# LCD_TFT.net
KiCad netlist of a schematic drawn in Altium Designer
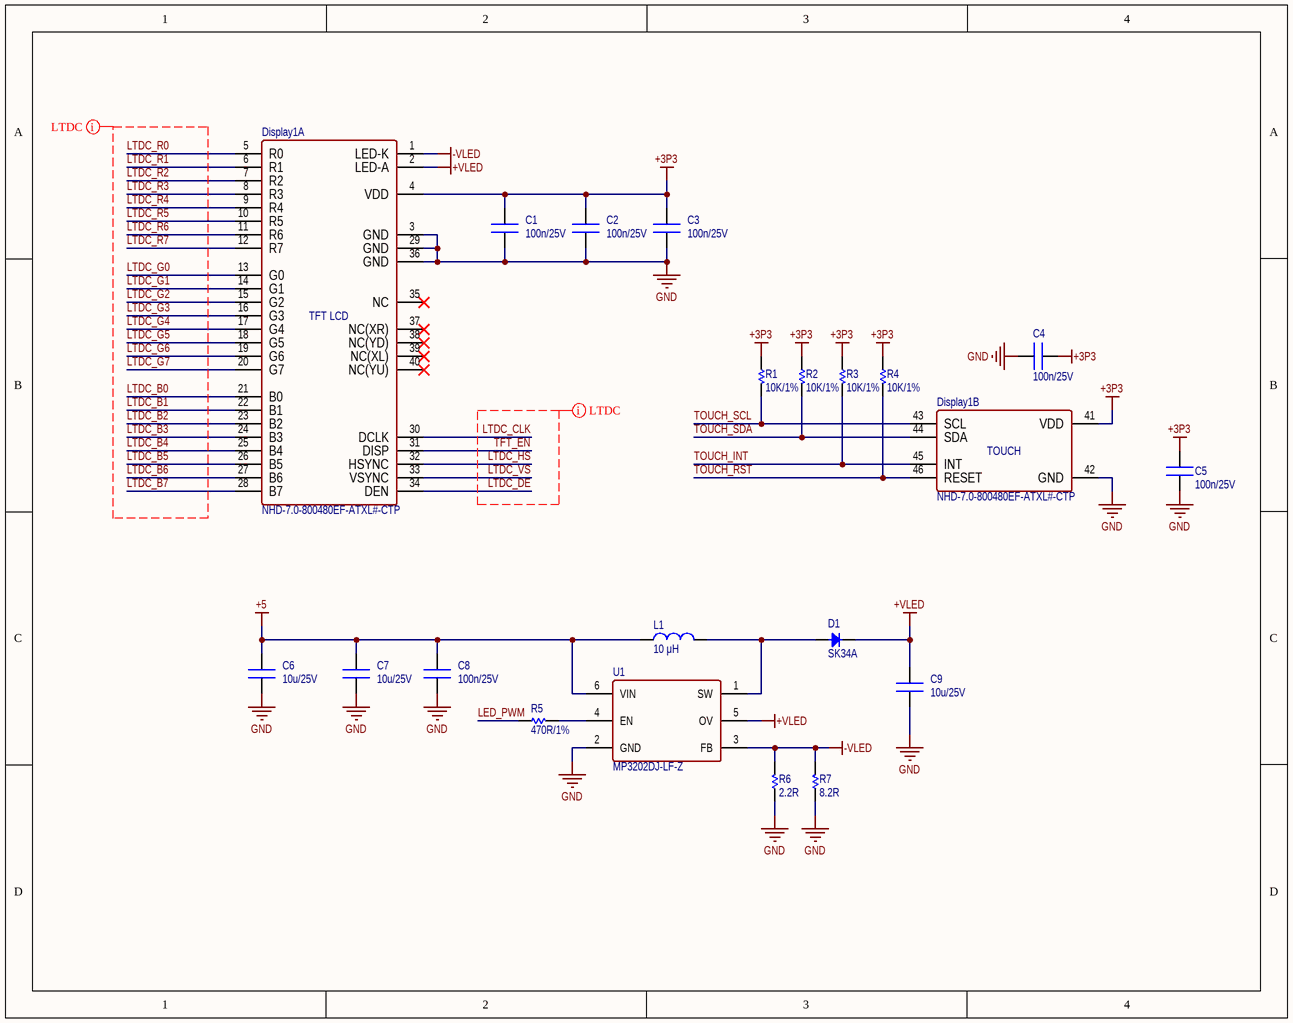
[diagram p0: LCD_TFT.SchDoc]

(export (version "E")
  (design (tool "Eeschema 10.0.6"))
  (components
    (comp (ref "C1")
      (value "100n/25V")
      (footprint "CN-SMD-0603")
      (description "CL10B104KA8NNNC")
      (libsource (lib "Library") (part "CN"))
    )
    (comp (ref "C2")
      (value "100n/25V")
      (footprint "CN-SMD-0603")
      (description "CL10B104KA8NNNC")
      (libsource (lib "Library") (part "CN"))
    )
    (comp (ref "C3")
      (value "100n/25V")
      (footprint "CN-SMD-0603")
      (description "CL10B104KA8NNNC")
      (libsource (lib "Library") (part "CN"))
    )
    (comp (ref "C4")
      (value "100n/25V")
      (footprint "CN-SMD-0603")
      (description "CL10B104KA8NNNC")
      (libsource (lib "Library") (part "CN"))
    )
    (comp (ref "C5")
      (value "100n/25V")
      (footprint "CN-SMD-0603")
      (description "CL10B104KA8NNNC")
      (libsource (lib "Library") (part "CN"))
    )
    (comp (ref "C6")
      (value "10u/25V")
      (footprint "CN-SMD-0603")
      (description "0603W106M250XD")
      (libsource (lib "Library") (part "CN"))
    )
    (comp (ref "C7")
      (value "10u/25V")
      (footprint "CN-SMD-0603")
      (description "0603W106M250XD")
      (libsource (lib "Library") (part "CN"))
    )
    (comp (ref "C8")
      (value "100n/25V")
      (footprint "CN-SMD-0603")
      (description "CL10B104KA8NNNC")
      (libsource (lib "Library") (part "CN"))
    )
    (comp (ref "C9")
      (value "10u/25V")
      (footprint "CN-SMD-0603")
      (description "0603W106M250XD")
      (libsource (lib "Library") (part "CN"))
    )
    (comp (ref "D1")
      (value "SK34A")
      (footprint "DIO-SMD-A")
      (fields (field (name "PUBLISHER") "Altium Limited"))
      (libsource (lib "Library") (part "Diode SMD"))
    )
    (comp (ref "Display1")
      (value "NHD-7.0-800480EF-ATXL#-CTP")
      (footprint "NHD-7.0-800480EF-ATXL#-CTP")
      (description "TFT (Thin-Film-Transistor) Color Liquid Crystal Display Module, 0541044031 + 52271-0679")
      (libsource (lib "Library") (part "NHD-7.0-800480EF-ATXL#-CTP"))
    )
    (comp (ref "L1")
      (value "10 μH")
      (footprint "L-SMD-M-5x5")
      (description "NRS5024T100MMGJ")
      (fields (field (name "MANUFACTURER") "Wurth Elektronik") (field (name "CREATED BY") "Baojun Chen"))
      (libsource (lib "Library") (part "L-SMD-1"))
    )
    (comp (ref "R1")
      (value "10K/1%")
      (footprint "RES-SMD-0603")
      (description "ERJ-3EKF1002V")
      (fields
        (field (name "MANUFACTURER") "Generic Components")
        (field (name "PUBLISHER") "Altium Hobart Technology Centre")
      )
      (libsource (lib "Library") (part "Res-SMD"))
    )
    (comp (ref "R2")
      (value "10K/1%")
      (footprint "RES-SMD-0603")
      (description "ERJ-3EKF1002V")
      (fields
        (field (name "MANUFACTURER") "Generic Components")
        (field (name "PUBLISHER") "Altium Hobart Technology Centre")
      )
      (libsource (lib "Library") (part "Res-SMD"))
    )
    (comp (ref "R3")
      (value "10K/1%")
      (footprint "RES-SMD-0603")
      (description "ERJ-3EKF1002V")
      (fields
        (field (name "MANUFACTURER") "Generic Components")
        (field (name "PUBLISHER") "Altium Hobart Technology Centre")
      )
      (libsource (lib "Library") (part "Res-SMD"))
    )
    (comp (ref "R4")
      (value "10K/1%")
      (footprint "RES-SMD-0603")
      (description "ERJ-3EKF1002V")
      (fields
        (field (name "MANUFACTURER") "Generic Components")
        (field (name "PUBLISHER") "Altium Hobart Technology Centre")
      )
      (libsource (lib "Library") (part "Res-SMD"))
    )
    (comp (ref "R5")
      (value "470R/1%")
      (footprint "RES-SMD-0603")
      (description "ERJ-1GJF4700C")
      (fields
        (field (name "MANUFACTURER") "Generic Components")
        (field (name "PUBLISHER") "Altium Hobart Technology Centre")
      )
      (libsource (lib "Library") (part "Res-SMD"))
    )
    (comp (ref "R6")
      (value "2.2R")
      (footprint "RES-SMD-0805")
      (description "RMCF0805JT2R20")
      (fields
        (field (name "MANUFACTURER") "Generic Components")
        (field (name "PUBLISHER") "Altium Hobart Technology Centre")
      )
      (libsource (lib "Library") (part "Res-SMD"))
    )
    (comp (ref "R7")
      (value "8.2R")
      (footprint "RES-SMD-0805")
      (description "RMCF0805FT8R20")
      (fields
        (field (name "MANUFACTURER") "Generic Components")
        (field (name "PUBLISHER") "Altium Hobart Technology Centre")
      )
      (libsource (lib "Library") (part "Res-SMD"))
    )
    (comp (ref "U1")
      (value "MP3202DJ-LF-Z")
      (footprint "SOT23-6")
      (description "1.3A Fixed Frequency White LED Driver")
      (libsource (lib "Library") (part "MP3202"))
    )
  )
  (nets
    (net (code "1") (name "+3P3") (class "Default")
      (node (ref "C1") (pin "2") (pinfunction "2_2") (pintype "passive"))
      (node (ref "C2") (pin "2") (pinfunction "2_2") (pintype "passive"))
      (node (ref "C3") (pin "2") (pinfunction "2_2") (pintype "passive"))
      (node (ref "C4") (pin "2") (pinfunction "2_2") (pintype "passive"))
      (node (ref "C5") (pin "2") (pinfunction "2_2") (pintype "passive"))
      (node (ref "Display1") (pin "4") (pinfunction "VDD_4") (pintype "passive"))
      (node (ref "Display1") (pin "41") (pinfunction "VDD_41") (pintype "passive"))
      (node (ref "R1") (pin "1") (pinfunction "1_1") (pintype "passive"))
      (node (ref "R2") (pin "1") (pinfunction "1_1") (pintype "passive"))
      (node (ref "R3") (pin "1") (pinfunction "1_1") (pintype "passive"))
      (node (ref "R4") (pin "1") (pinfunction "1_1") (pintype "passive"))
    )
    (net (code "2") (name "+5") (class "Default")
      (node (ref "C6") (pin "2") (pinfunction "2_2") (pintype "passive"))
      (node (ref "C7") (pin "2") (pinfunction "2_2") (pintype "passive"))
      (node (ref "C8") (pin "2") (pinfunction "2_2") (pintype "passive"))
      (node (ref "L1") (pin "1") (pinfunction "1_1") (pintype "passive"))
      (node (ref "U1") (pin "6") (pinfunction "VIN_6") (pintype "passive"))
    )
    (net (code "3") (name "+VLED") (class "Default")
      (node (ref "C9") (pin "2") (pinfunction "2_2") (pintype "passive"))
      (node (ref "D1") (pin "2") (pinfunction "K_2") (pintype "passive"))
      (node (ref "Display1") (pin "2") (pinfunction "LED-A_2") (pintype "passive"))
      (node (ref "U1") (pin "5") (pinfunction "OV_5") (pintype "passive"))
    )
    (net (code "4") (name "-VLED") (class "Default")
      (node (ref "Display1") (pin "1") (pinfunction "LED-K_1") (pintype "passive"))
      (node (ref "R6") (pin "2") (pinfunction "2_2") (pintype "passive"))
      (node (ref "R7") (pin "2") (pinfunction "2_2") (pintype "passive"))
      (node (ref "U1") (pin "3") (pinfunction "FB_3") (pintype "passive"))
    )
    (net (code "5") (name "/LED_PWM") (class "Default")
      (node (ref "R5") (pin "1") (pinfunction "1_1") (pintype "passive"))
    )
    (net (code "6") (name "/LTDC_B0") (class "Default")
      (node (ref "Display1") (pin "21") (pinfunction "B0_21") (pintype "passive"))
    )
    (net (code "7") (name "/LTDC_B1") (class "Default")
      (node (ref "Display1") (pin "22") (pinfunction "B1_22") (pintype "passive"))
    )
    (net (code "8") (name "/LTDC_B2") (class "Default")
      (node (ref "Display1") (pin "23") (pinfunction "B2_23") (pintype "passive"))
    )
    (net (code "9") (name "/LTDC_B3") (class "Default")
      (node (ref "Display1") (pin "24") (pinfunction "B3_24") (pintype "passive"))
    )
    (net (code "10") (name "/LTDC_B4") (class "Default")
      (node (ref "Display1") (pin "25") (pinfunction "B4_25") (pintype "passive"))
    )
    (net (code "11") (name "/LTDC_B5") (class "Default")
      (node (ref "Display1") (pin "26") (pinfunction "B5_26") (pintype "passive"))
    )
    (net (code "12") (name "/LTDC_B6") (class "Default")
      (node (ref "Display1") (pin "27") (pinfunction "B6_27") (pintype "passive"))
    )
    (net (code "13") (name "/LTDC_B7") (class "Default")
      (node (ref "Display1") (pin "28") (pinfunction "B7_28") (pintype "passive"))
    )
    (net (code "14") (name "/LTDC_CLK") (class "Default")
      (node (ref "Display1") (pin "30") (pinfunction "DCLK_30") (pintype "passive"))
    )
    (net (code "15") (name "/LTDC_DE") (class "Default")
      (node (ref "Display1") (pin "34") (pinfunction "DEN_34") (pintype "passive"))
    )
    (net (code "16") (name "/LTDC_G0") (class "Default")
      (node (ref "Display1") (pin "13") (pinfunction "G0_13") (pintype "passive"))
    )
    (net (code "17") (name "/LTDC_G1") (class "Default")
      (node (ref "Display1") (pin "14") (pinfunction "G1_14") (pintype "passive"))
    )
    (net (code "18") (name "/LTDC_G2") (class "Default")
      (node (ref "Display1") (pin "15") (pinfunction "G2_15") (pintype "passive"))
    )
    (net (code "19") (name "/LTDC_G3") (class "Default")
      (node (ref "Display1") (pin "16") (pinfunction "G3_16") (pintype "passive"))
    )
    (net (code "20") (name "/LTDC_G4") (class "Default")
      (node (ref "Display1") (pin "17") (pinfunction "G4_17") (pintype "passive"))
    )
    (net (code "21") (name "/LTDC_G5") (class "Default")
      (node (ref "Display1") (pin "18") (pinfunction "G5_18") (pintype "passive"))
    )
    (net (code "22") (name "/LTDC_G6") (class "Default")
      (node (ref "Display1") (pin "19") (pinfunction "G6_19") (pintype "passive"))
    )
    (net (code "23") (name "/LTDC_G7") (class "Default")
      (node (ref "Display1") (pin "20") (pinfunction "G7_20") (pintype "passive"))
    )
    (net (code "24") (name "/LTDC_HS") (class "Default")
      (node (ref "Display1") (pin "32") (pinfunction "HSYNC_32") (pintype "passive"))
    )
    (net (code "25") (name "/LTDC_R0") (class "Default")
      (node (ref "Display1") (pin "5") (pinfunction "R0_5") (pintype "passive"))
    )
    (net (code "26") (name "/LTDC_R1") (class "Default")
      (node (ref "Display1") (pin "6") (pinfunction "R1_6") (pintype "passive"))
    )
    (net (code "27") (name "/LTDC_R2") (class "Default")
      (node (ref "Display1") (pin "7") (pinfunction "R2_7") (pintype "passive"))
    )
    (net (code "28") (name "/LTDC_R3") (class "Default")
      (node (ref "Display1") (pin "8") (pinfunction "R3_8") (pintype "passive"))
    )
    (net (code "29") (name "/LTDC_R4") (class "Default")
      (node (ref "Display1") (pin "9") (pinfunction "R4_9") (pintype "passive"))
    )
    (net (code "30") (name "/LTDC_R5") (class "Default")
      (node (ref "Display1") (pin "10") (pinfunction "R5_10") (pintype "passive"))
    )
    (net (code "31") (name "/LTDC_R6") (class "Default")
      (node (ref "Display1") (pin "11") (pinfunction "R6_11") (pintype "passive"))
    )
    (net (code "32") (name "/LTDC_R7") (class "Default")
      (node (ref "Display1") (pin "12") (pinfunction "R7_12") (pintype "passive"))
    )
    (net (code "33") (name "/LTDC_VS") (class "Default")
      (node (ref "Display1") (pin "33") (pinfunction "VSYNC_33") (pintype "passive"))
    )
    (net (code "34") (name "/TFT_EN") (class "Default")
      (node (ref "Display1") (pin "31") (pinfunction "DISP_31") (pintype "passive"))
    )
    (net (code "35") (name "/TOUCH_INT") (class "Default")
      (node (ref "Display1") (pin "45") (pinfunction "INT_45") (pintype "passive"))
      (node (ref "R3") (pin "2") (pinfunction "2_2") (pintype "passive"))
    )
    (net (code "36") (name "/TOUCH_RST") (class "Default")
      (node (ref "Display1") (pin "46") (pinfunction "RESET_46") (pintype "passive"))
      (node (ref "R4") (pin "2") (pinfunction "2_2") (pintype "passive"))
    )
    (net (code "37") (name "/TOUCH_SCL") (class "Default")
      (node (ref "Display1") (pin "43") (pinfunction "SCL_43") (pintype "passive"))
      (node (ref "R1") (pin "2") (pinfunction "2_2") (pintype "passive"))
    )
    (net (code "38") (name "/TOUCH_SDA") (class "Default")
      (node (ref "Display1") (pin "44") (pinfunction "SDA_44") (pintype "passive"))
      (node (ref "R2") (pin "2") (pinfunction "2_2") (pintype "passive"))
    )
    (net (code "39") (name "GND") (class "Default")
      (node (ref "C1") (pin "1") (pinfunction "1_1") (pintype "passive"))
      (node (ref "C2") (pin "1") (pinfunction "1_1") (pintype "passive"))
      (node (ref "C3") (pin "1") (pinfunction "1_1") (pintype "passive"))
      (node (ref "C4") (pin "1") (pinfunction "1_1") (pintype "passive"))
      (node (ref "C5") (pin "1") (pinfunction "1_1") (pintype "passive"))
      (node (ref "C6") (pin "1") (pinfunction "1_1") (pintype "passive"))
      (node (ref "C7") (pin "1") (pinfunction "1_1") (pintype "passive"))
      (node (ref "C8") (pin "1") (pinfunction "1_1") (pintype "passive"))
      (node (ref "C9") (pin "1") (pinfunction "1_1") (pintype "passive"))
      (node (ref "Display1") (pin "29") (pinfunction "GND_29") (pintype "passive"))
      (node (ref "Display1") (pin "3") (pinfunction "GND_3") (pintype "passive"))
      (node (ref "Display1") (pin "36") (pinfunction "GND_36") (pintype "passive"))
      (node (ref "Display1") (pin "42") (pinfunction "GND_42") (pintype "passive"))
      (node (ref "R6") (pin "1") (pinfunction "1_1") (pintype "passive"))
      (node (ref "R7") (pin "1") (pinfunction "1_1") (pintype "passive"))
      (node (ref "U1") (pin "2") (pinfunction "GND_2") (pintype "passive"))
    )
    (net (code "40") (name "Net-(D1-A)") (class "Default")
      (node (ref "D1") (pin "1") (pinfunction "A_1") (pintype "passive"))
      (node (ref "L1") (pin "2") (pinfunction "2_2") (pintype "passive"))
      (node (ref "U1") (pin "1") (pinfunction "SW_1") (pintype "passive"))
    )
    (net (code "41") (name "Net-(U1-EN)") (class "Default")
      (node (ref "R5") (pin "2") (pinfunction "2_2") (pintype "passive"))
      (node (ref "U1") (pin "4") (pinfunction "EN_4") (pintype "passive"))
    )
    (net (code "42") (name "unconnected-(Display1A-NC(XL)-Pad39)") (class "Default")
      (node (ref "Display1") (pin "39") (pinfunction "NC(XL)_39") (pintype "passive+no_connect"))
    )
    (net (code "43") (name "unconnected-(Display1A-NC(XR)-Pad37)") (class "Default")
      (node (ref "Display1") (pin "37") (pinfunction "NC(XR)_37") (pintype "passive+no_connect"))
    )
    (net (code "44") (name "unconnected-(Display1A-NC(YD)-Pad38)") (class "Default")
      (node (ref "Display1") (pin "38") (pinfunction "NC(YD)_38") (pintype "passive+no_connect"))
    )
    (net (code "45") (name "unconnected-(Display1A-NC(YU)-Pad40)") (class "Default")
      (node (ref "Display1") (pin "40") (pinfunction "NC(YU)_40") (pintype "passive+no_connect"))
    )
    (net (code "46") (name "unconnected-(Display1A-NC-Pad35)") (class "Default")
      (node (ref "Display1") (pin "35") (pinfunction "NC_35") (pintype "passive+no_connect"))
    )
  )
)
